# FNR_Controller_v1_1_-_Relay.net
KiCad netlist of a schematic drawn in EAGLE
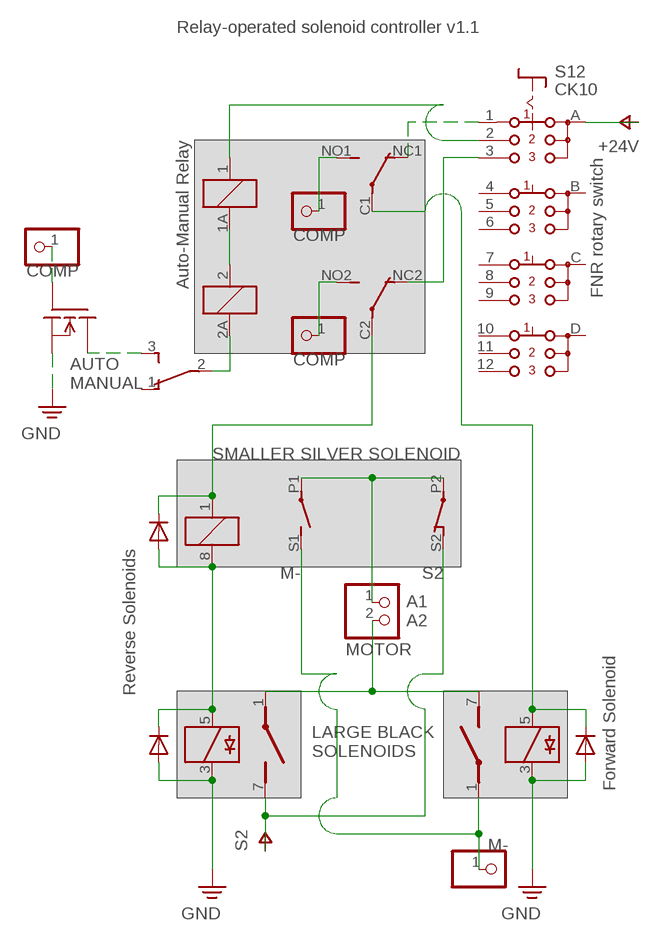
[diagram p0: schematic, sheet 1]

(export (version "E")
  (design (tool "Eeschema 10.0.6"))
  (components
    (comp (ref "D4")
      (value "1N4004")
      (footprint "eagle-import:DO41-10")
      (libsource (lib "eagle-import") (part "1N4004"))
    )
    (comp (ref "D5")
      (value "1N4004")
      (footprint "eagle-import:DO41-10")
      (libsource (lib "eagle-import") (part "1N4004"))
    )
    (comp (ref "D6")
      (value "1N4004")
      (footprint "eagle-import:DO41-10")
      (libsource (lib "eagle-import") (part "1N4004"))
    )
    (comp (ref "JP12")
      (value "COMP")
      (footprint "eagle-import:1X01")
      (libsource (lib "eagle-import") (part "PINHD-1X1"))
    )
    (comp (ref "JP18")
      (value "MOTOR")
      (footprint "eagle-import:1X02")
      (libsource (lib "eagle-import") (part "PINHD-1X2"))
    )
    (comp (ref "JP19")
      (value "M-")
      (footprint "eagle-import:1X01")
      (libsource (lib "eagle-import") (part "PINHD-1X1"))
    )
    (comp (ref "JP20")
      (value "COMP")
      (footprint "eagle-import:1X01")
      (libsource (lib "eagle-import") (part "PINHD-1X1"))
    )
    (comp (ref "JP21")
      (value "COMP")
      (footprint "eagle-import:1X01")
      (libsource (lib "eagle-import") (part "PINHD-1X1"))
    )
    (comp (ref "K11")
      (value "CT512")
      (footprint "eagle-import:CT2-TWIN")
      (libsource (lib "eagle-import") (part "CT512"))
    )
    (comp (ref "K12")
      (value "35701331")
      (footprint "eagle-import:REED")
      (libsource (lib "eagle-import") (part "35701331"))
    )
    (comp (ref "K13")
      (value "35701331")
      (footprint "eagle-import:REED")
      (libsource (lib "eagle-import") (part "35701331"))
    )
    (comp (ref "K14")
      (value "G6C-2117P")
      (footprint "eagle-import:G6C-2117P")
      (libsource (lib "eagle-import") (part "G6C-2117P"))
    )
    (comp (ref "Q3")
      (value "BUZ11")
      (footprint "eagle-import:TO220")
      (libsource (lib "eagle-import") (part "BUZ11"))
    )
    (comp (ref "S11")
      (value "M-A")
      (footprint "eagle-import:TL3XPO")
      (libsource (lib "eagle-import") (part "TL36PO"))
    )
    (comp (ref "S12")
      (value "CK10")
      (footprint "eagle-import:CK10")
      (libsource (lib "eagle-import") (part "CK10"))
    )
  )
  (nets
    (net (code "1") (name "+24V") (class "Default")
      (node (ref "K12") (pin "7") (pinfunction "S_7") (pintype "passive"))
      (node (ref "K14") (pin "S2") (pinfunction "O_S2") (pintype "passive"))
      (node (ref "S12") (pin "A") (pinfunction "A_A") (pintype "passive"))
    )
    (net (code "2") (name "/M-") (class "Default")
      (node (ref "JP19") (pin "1") (pinfunction "1_1") (pintype "passive"))
      (node (ref "K13") (pin "1") (pinfunction "P_1") (pintype "passive"))
      (node (ref "K14") (pin "S1") (pinfunction "S_S1") (pintype "passive"))
    )
    (net (code "3") (name "GND") (class "Default")
      (node (ref "D4") (pin "A") (pinfunction "A_A") (pintype "passive"))
      (node (ref "D6") (pin "A") (pinfunction "A_A") (pintype "passive"))
      (node (ref "K12") (pin "3") (pinfunction "3_3") (pintype "passive"))
      (node (ref "K13") (pin "3") (pinfunction "3_3") (pintype "passive"))
      (node (ref "Q3") (pin "3") (pinfunction "S_3") (pintype "passive"))
    )
    (net (code "4") (name "Net-(K11A-2)") (class "Default")
      (node (ref "K11") (pin "1A") (pinfunction "2_1A") (pintype "passive"))
      (node (ref "K11") (pin "2") (pinfunction "1_2") (pintype "passive"))
    )
    (net (code "5") (name "Net-(K11B-O)") (class "Default")
      (node (ref "K11") (pin "NC1") (pinfunction "O_NC1") (pintype "passive"))
      (node (ref "S12") (pin "1") (pinfunction "A1_1") (pintype "passive"))
    )
    (net (code "6") (name "Net-(K11B-P)") (class "Default")
      (node (ref "D6") (pin "C") (pinfunction "C_C") (pintype "passive"))
      (node (ref "K11") (pin "C1") (pinfunction "P_C1") (pintype "passive"))
      (node (ref "K13") (pin "5") (pinfunction "5_5") (pintype "passive"))
    )
    (net (code "7") (name "Net-(K11B-S)") (class "Default")
      (node (ref "JP12") (pin "1") (pinfunction "1_1") (pintype "passive"))
      (node (ref "K11") (pin "NO1") (pinfunction "S_NO1") (pintype "passive"))
    )
    (net (code "8") (name "Net-(K11C-2)") (class "Default")
      (node (ref "K11") (pin "2A") (pinfunction "2_2A") (pintype "passive"))
      (node (ref "S11") (pin "2") (pinfunction "P_2") (pintype "passive"))
    )
    (net (code "9") (name "Net-(K11D-O)") (class "Default")
      (node (ref "K11") (pin "NC2") (pinfunction "O_NC2") (pintype "passive"))
      (node (ref "S12") (pin "3") (pinfunction "A3_3") (pintype "passive"))
    )
    (net (code "10") (name "Net-(K11D-P)") (class "Default")
      (node (ref "D5") (pin "C") (pinfunction "C_C") (pintype "passive"))
      (node (ref "K11") (pin "C2") (pinfunction "P_C2") (pintype "passive"))
      (node (ref "K14") (pin "1") (pinfunction "1_1") (pintype "passive"))
    )
    (net (code "11") (name "Net-(K11D-S)") (class "Default")
      (node (ref "JP20") (pin "1") (pinfunction "1_1") (pintype "passive"))
      (node (ref "K11") (pin "NO2") (pinfunction "S_NO2") (pintype "passive"))
    )
    (net (code "12") (name "Net-(K12B-P)") (class "Default")
      (node (ref "JP18") (pin "2") (pinfunction "2_2") (pintype "passive"))
      (node (ref "K12") (pin "1") (pinfunction "P_1") (pintype "passive"))
      (node (ref "K13") (pin "7") (pinfunction "S_7") (pintype "passive"))
    )
    (net (code "13") (name "Net-(K14A-2)") (class "Default")
      (node (ref "D4") (pin "C") (pinfunction "C_C") (pintype "passive"))
      (node (ref "D5") (pin "A") (pinfunction "A_A") (pintype "passive"))
      (node (ref "K12") (pin "5") (pinfunction "5_5") (pintype "passive"))
      (node (ref "K14") (pin "8") (pinfunction "2_8") (pintype "passive"))
    )
    (net (code "14") (name "Net-(K14B-P)") (class "Default")
      (node (ref "JP18") (pin "1") (pinfunction "1_1") (pintype "passive"))
      (node (ref "K14") (pin "P1") (pinfunction "P_P1") (pintype "passive"))
      (node (ref "K14") (pin "P2") (pinfunction "P_P2") (pintype "passive"))
    )
    (net (code "15") (name "Net-(Q3-D)") (class "Default")
      (node (ref "Q3") (pin "2") (pinfunction "D_2") (pintype "passive"))
      (node (ref "S11") (pin "3") (pinfunction "S_3") (pintype "passive"))
    )
    (net (code "16") (name "Net-(Q3-G)") (class "Default")
      (node (ref "JP21") (pin "1") (pinfunction "1_1") (pintype "passive"))
      (node (ref "Q3") (pin "1") (pinfunction "G_1") (pintype "passive"))
    )
    (net (code "17") (name "Net-(S12-A2)") (class "Default")
      (node (ref "K11") (pin "1") (pinfunction "1_1") (pintype "passive"))
      (node (ref "S12") (pin "2") (pinfunction "A2_2") (pintype "passive"))
    )
    (net (code "18") (name "unconnected-(S11-O-Pad1)") (class "Default")
      (node (ref "S11") (pin "1") (pinfunction "O_1") (pintype "passive"))
    )
    (net (code "19") (name "unconnected-(S12-B1-Pad4)") (class "Default")
      (node (ref "S12") (pin "4") (pinfunction "B1_4") (pintype "passive"))
    )
    (net (code "20") (name "unconnected-(S12-B2-Pad5)") (class "Default")
      (node (ref "S12") (pin "5") (pinfunction "B2_5") (pintype "passive"))
    )
    (net (code "21") (name "unconnected-(S12-B3-Pad6)") (class "Default")
      (node (ref "S12") (pin "6") (pinfunction "B3_6") (pintype "passive"))
    )
    (net (code "22") (name "unconnected-(S12-C1-Pad7)") (class "Default")
      (node (ref "S12") (pin "7") (pinfunction "C1_7") (pintype "passive"))
    )
    (net (code "23") (name "unconnected-(S12-C2-Pad8)") (class "Default")
      (node (ref "S12") (pin "8") (pinfunction "C2_8") (pintype "passive"))
    )
    (net (code "24") (name "unconnected-(S12-C3-Pad9)") (class "Default")
      (node (ref "S12") (pin "9") (pinfunction "C3_9") (pintype "passive"))
    )
    (net (code "25") (name "unconnected-(S12-D1-Pad10)") (class "Default")
      (node (ref "S12") (pin "10") (pinfunction "D1_10") (pintype "passive"))
    )
    (net (code "26") (name "unconnected-(S12-D2-Pad11)") (class "Default")
      (node (ref "S12") (pin "11") (pinfunction "D2_11") (pintype "passive"))
    )
    (net (code "27") (name "unconnected-(S12-D3-Pad12)") (class "Default")
      (node (ref "S12") (pin "12") (pinfunction "D3_12") (pintype "passive"))
    )
    (net (code "28") (name "unconnected-(S12-PadB)") (class "Default")
      (node (ref "S12") (pin "B") (pinfunction "B_B") (pintype "passive"))
    )
    (net (code "29") (name "unconnected-(S12-PadC)") (class "Default")
      (node (ref "S12") (pin "C") (pinfunction "C_C") (pintype "passive"))
    )
    (net (code "30") (name "unconnected-(S12-PadD)") (class "Default")
      (node (ref "S12") (pin "D") (pinfunction "D_D") (pintype "passive"))
    )
  )
)
